# Power.net
KiCad netlist of a schematic drawn in Altium Designer
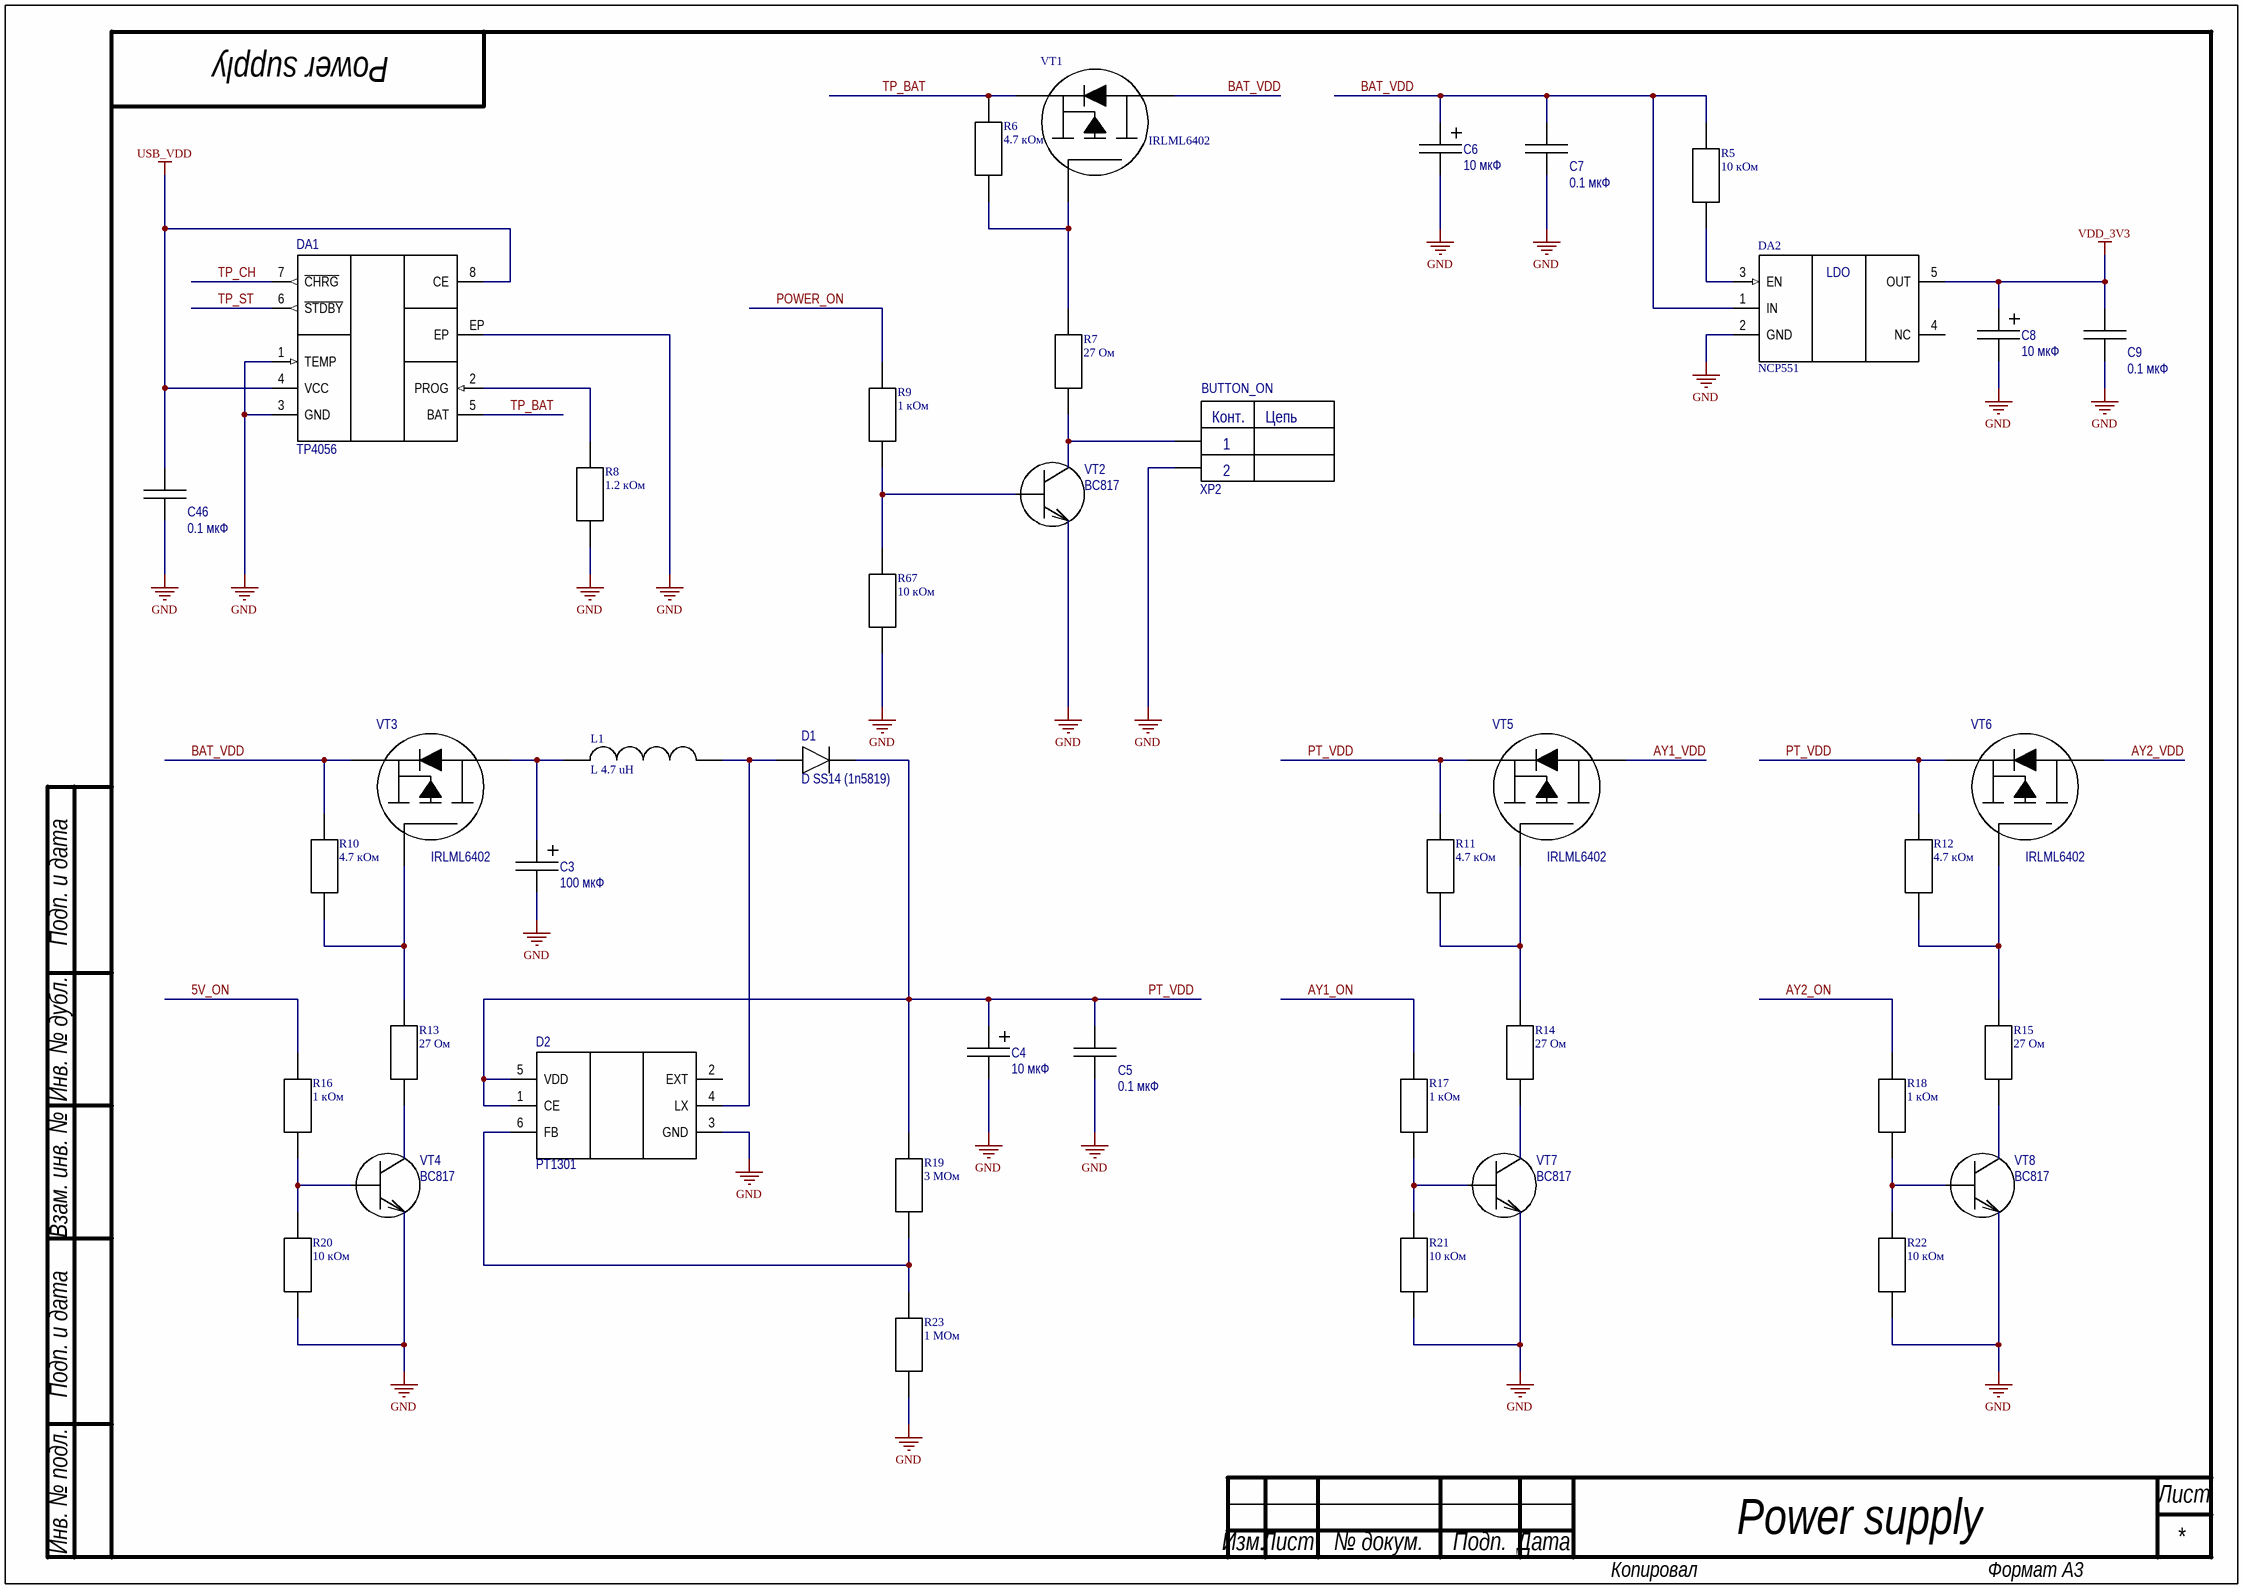
[diagram p0: Power.SchDoc]

(export (version "E")
  (design (tool "Eeschema 10.0.6"))
  (components
    (comp (ref "C3")
      (value "100 мкФ")
      (footprint "C TAN_D")
      (description "SMD Tantalium Capacitor D")
      (fields
        (field (name "TOLERANCE") "/Укажите допуск в процентах/")
        (field (name "MANUFACTURER") "/Укажите компанию-производителя/")
      )
      (libsource (lib "my_lib") (part "CAP TAN_D"))
    )
    (comp (ref "C4")
      (value "10 мкФ")
      (footprint "C TAN_C")
      (description "SMD Tantalium Capacitor C")
      (fields
        (field (name "TOLERANCE") "/Укажите допуск в процентах/")
        (field (name "MANUFACTURER") "/Укажите компанию-производителя/")
      )
      (libsource (lib "my_lib") (part "CAP TAN_C"))
    )
    (comp (ref "C5")
      (value "0.1 мкФ")
      (footprint "C 1206")
      (description "SMD Capacitor 1206")
      (fields
        (field (name "TOLERANCE") "/Укажите допуск в процентах/")
        (field (name "MANUFACTURER") "/Укажите компанию-производителя/")
      )
      (libsource (lib "my_lib") (part "CAP 1206"))
    )
    (comp (ref "C6")
      (value "10 мкФ")
      (footprint "C TAN_C")
      (description "SMD Tantalium Capacitor C")
      (fields
        (field (name "TOLERANCE") "/Укажите допуск в процентах/")
        (field (name "MANUFACTURER") "/Укажите компанию-производителя/")
      )
      (libsource (lib "my_lib") (part "CAP TAN_C"))
    )
    (comp (ref "C7")
      (value "0.1 мкФ")
      (footprint "C 1206")
      (description "SMD Capacitor 1206")
      (fields
        (field (name "TOLERANCE") "/Укажите допуск в процентах/")
        (field (name "MANUFACTURER") "/Укажите компанию-производителя/")
      )
      (libsource (lib "my_lib") (part "CAP 1206"))
    )
    (comp (ref "C8")
      (value "10 мкФ")
      (footprint "C TAN_C")
      (description "SMD Tantalium Capacitor C")
      (fields
        (field (name "TOLERANCE") "/Укажите допуск в процентах/")
        (field (name "MANUFACTURER") "/Укажите компанию-производителя/")
      )
      (libsource (lib "my_lib") (part "CAP TAN_C"))
    )
    (comp (ref "C9")
      (value "0.1 мкФ")
      (footprint "C 1206")
      (description "SMD Capacitor 1206")
      (fields
        (field (name "TOLERANCE") "/Укажите допуск в процентах/")
        (field (name "MANUFACTURER") "/Укажите компанию-производителя/")
      )
      (libsource (lib "my_lib") (part "CAP 1206"))
    )
    (comp (ref "C46")
      (value "0.1 мкФ")
      (footprint "C 1206")
      (description "SMD Capacitor 1206")
      (fields
        (field (name "TOLERANCE") "/Укажите допуск в процентах/")
        (field (name "MANUFACTURER") "/Укажите компанию-производителя/")
      )
      (libsource (lib "my_lib") (part "CAP 1206"))
    )
    (comp (ref "D1")
      (value "D SS14 (1n5819)")
      (footprint "SMA/DO-214AC")
      (libsource (lib "my_lib") (part "D SS14 (1n5819)"))
    )
    (comp (ref "D2")
      (value "PT1301")
      (footprint "SOT-23-6")
      (description "DC-DC step-up (повышающий) PT1301 в корпусе SOT23-6.")
      (libsource (lib "my_lib") (part "PT1301"))
    )
    (comp (ref "DA1") (value "TP4056") (footprint "HSOP-8") (libsource (lib "my_lib") (part "TP4056")))
    (comp (ref "DA2") (value "NCP551") (footprint "TSOP-5") (libsource (lib "my_lib") (part "NCP551")))
    (comp (ref "L1")
      (value "L 4.7 uH")
      (footprint "CD43")
      (description "Катушка индуктивности 4.7 мкГн корпус CD43 (индуктивность 4.7 uH).")
      (libsource (lib "my_lib") (part "L 4.7 uH"))
    )
    (comp (ref "R5") (value "10 кОм") (footprint "RES 0805") (libsource (lib "my_lib") (part "RES 0805")))
    (comp (ref "R6") (value "4.7 кОм") (footprint "RES 0805") (libsource (lib "my_lib") (part "RES 0805")))
    (comp (ref "R7") (value "27 Ом") (footprint "RES 0805") (libsource (lib "my_lib") (part "RES 0805")))
    (comp (ref "R8") (value "1.2 кОм") (footprint "RES 0805") (libsource (lib "my_lib") (part "RES 0805")))
    (comp (ref "R9") (value "1 кОм") (footprint "RES 0805") (libsource (lib "my_lib") (part "RES 0805")))
    (comp (ref "R10") (value "4.7 кОм") (footprint "RES 0805") (libsource (lib "my_lib") (part "RES 0805")))
    (comp (ref "R11") (value "4.7 кОм") (footprint "RES 0805") (libsource (lib "my_lib") (part "RES 0805")))
    (comp (ref "R12") (value "4.7 кОм") (footprint "RES 0805") (libsource (lib "my_lib") (part "RES 0805")))
    (comp (ref "R13") (value "27 Ом") (footprint "RES 0805") (libsource (lib "my_lib") (part "RES 0805")))
    (comp (ref "R14") (value "27 Ом") (footprint "RES 0805") (libsource (lib "my_lib") (part "RES 0805")))
    (comp (ref "R15") (value "27 Ом") (footprint "RES 0805") (libsource (lib "my_lib") (part "RES 0805")))
    (comp (ref "R16") (value "1 кОм") (footprint "RES 0805") (libsource (lib "my_lib") (part "RES 0805")))
    (comp (ref "R17") (value "1 кОм") (footprint "RES 0805") (libsource (lib "my_lib") (part "RES 0805")))
    (comp (ref "R18") (value "1 кОм") (footprint "RES 0805") (libsource (lib "my_lib") (part "RES 0805")))
    (comp (ref "R19") (value "3 МОм") (footprint "RES 0805") (libsource (lib "my_lib") (part "RES 0805")))
    (comp (ref "R20") (value "10 кОм") (footprint "RES 0805") (libsource (lib "my_lib") (part "RES 0805")))
    (comp (ref "R21") (value "10 кОм") (footprint "RES 0805") (libsource (lib "my_lib") (part "RES 0805")))
    (comp (ref "R22") (value "10 кОм") (footprint "RES 0805") (libsource (lib "my_lib") (part "RES 0805")))
    (comp (ref "R23") (value "1 МОм") (footprint "RES 0805") (libsource (lib "my_lib") (part "RES 0805")))
    (comp (ref "R67") (value "10 кОм") (footprint "RES 0805") (libsource (lib "my_lib") (part "RES 0805")))
    (comp (ref "VT1") (value "IRLML6402") (footprint "SOT-23") (libsource (lib "my_lib") (part "IRLML6402")))
    (comp (ref "VT2")
      (value "BC817")
      (footprint "SOT-23")
      (description "NPN general-purpose transistor")
      (fields (field (name "MANUFACTURER") "NXP"))
      (libsource (lib "my_lib") (part "BC817"))
    )
    (comp (ref "VT3") (value "IRLML6402") (footprint "SOT-23") (libsource (lib "my_lib") (part "IRLML6402")))
    (comp (ref "VT4")
      (value "BC817")
      (footprint "SOT-23")
      (description "NPN general-purpose transistor")
      (fields (field (name "MANUFACTURER") "NXP"))
      (libsource (lib "my_lib") (part "BC817"))
    )
    (comp (ref "VT5") (value "IRLML6402") (footprint "SOT-23") (libsource (lib "my_lib") (part "IRLML6402")))
    (comp (ref "VT6") (value "IRLML6402") (footprint "SOT-23") (libsource (lib "my_lib") (part "IRLML6402")))
    (comp (ref "VT7")
      (value "BC817")
      (footprint "SOT-23")
      (description "NPN general-purpose transistor")
      (fields (field (name "MANUFACTURER") "NXP"))
      (libsource (lib "my_lib") (part "BC817"))
    )
    (comp (ref "VT8")
      (value "BC817")
      (footprint "SOT-23")
      (description "NPN general-purpose transistor")
      (fields (field (name "MANUFACTURER") "NXP"))
      (libsource (lib "my_lib") (part "BC817"))
    )
    (comp (ref "XP2")
      (value "PLS-2")
      (footprint "PLS-2")
      (description "PLS connector")
      (fields (field (name "MANUFACTURER") "NONAME"))
      (libsource (lib "my_lib") (part "PLS-2"))
    )
  )
  (nets
    (net (code "1") (name "/5V_ON") (class "Default")
      (node (ref "R16") (pin "2") (pinfunction "2_2") (pintype "passive"))
    )
    (net (code "2") (name "/AY1_ON") (class "Default")
      (node (ref "R17") (pin "2") (pinfunction "2_2") (pintype "passive"))
    )
    (net (code "3") (name "/AY1_VDD") (class "Default")
      (node (ref "VT5") (pin "3") (pinfunction "D_3") (pintype "passive"))
    )
    (net (code "4") (name "/AY2_ON") (class "Default")
      (node (ref "R18") (pin "2") (pinfunction "2_2") (pintype "passive"))
    )
    (net (code "5") (name "/AY2_VDD") (class "Default")
      (node (ref "VT6") (pin "3") (pinfunction "D_3") (pintype "passive"))
    )
    (net (code "6") (name "/BAT_VDD") (class "Default")
      (node (ref "C6") (pin "1") (pinfunction "1_1") (pintype "passive"))
      (node (ref "C7") (pin "1") (pinfunction "1_1") (pintype "passive"))
      (node (ref "DA2") (pin "1") (pinfunction "IN_1") (pintype "passive"))
      (node (ref "R10") (pin "2") (pinfunction "2_2") (pintype "passive"))
      (node (ref "R5") (pin "2") (pinfunction "2_2") (pintype "passive"))
      (node (ref "VT1") (pin "3") (pinfunction "D_3") (pintype "passive"))
      (node (ref "VT3") (pin "2") (pinfunction "S_2") (pintype "passive"))
    )
    (net (code "7") (name "/POWER_ON") (class "Default")
      (node (ref "R9") (pin "2") (pinfunction "2_2") (pintype "passive"))
    )
    (net (code "8") (name "/PT_VDD") (class "Default")
      (node (ref "C4") (pin "1") (pinfunction "1_1") (pintype "passive"))
      (node (ref "C5") (pin "1") (pinfunction "1_1") (pintype "passive"))
      (node (ref "D1") (pin "C") (pinfunction "C_C") (pintype "passive"))
      (node (ref "D2") (pin "1") (pinfunction "CE_1") (pintype "passive"))
      (node (ref "D2") (pin "5") (pinfunction "VDD_5") (pintype "passive"))
      (node (ref "R11") (pin "2") (pinfunction "2_2") (pintype "passive"))
      (node (ref "R12") (pin "2") (pinfunction "2_2") (pintype "passive"))
      (node (ref "R19") (pin "2") (pinfunction "2_2") (pintype "passive"))
      (node (ref "VT5") (pin "2") (pinfunction "S_2") (pintype "passive"))
      (node (ref "VT6") (pin "2") (pinfunction "S_2") (pintype "passive"))
    )
    (net (code "9") (name "/TP_BAT") (class "Default")
      (node (ref "DA1") (pin "5") (pinfunction "BAT_5") (pintype "power_in"))
      (node (ref "R6") (pin "2") (pinfunction "2_2") (pintype "passive"))
      (node (ref "VT1") (pin "2") (pinfunction "S_2") (pintype "passive"))
    )
    (net (code "10") (name "/TP_CH") (class "Default")
      (node (ref "DA1") (pin "7") (pinfunction "~{CHRG}_7") (pintype "output"))
    )
    (net (code "11") (name "/TP_ST") (class "Default")
      (node (ref "DA1") (pin "6") (pinfunction "~{STDBY}_6") (pintype "output"))
    )
    (net (code "12") (name "GND") (class "Default")
      (node (ref "C3") (pin "2") (pinfunction "2_2") (pintype "passive"))
      (node (ref "C4") (pin "2") (pinfunction "2_2") (pintype "passive"))
      (node (ref "C46") (pin "2") (pinfunction "2_2") (pintype "passive"))
      (node (ref "C5") (pin "2") (pinfunction "2_2") (pintype "passive"))
      (node (ref "C6") (pin "2") (pinfunction "2_2") (pintype "passive"))
      (node (ref "C7") (pin "2") (pinfunction "2_2") (pintype "passive"))
      (node (ref "C8") (pin "2") (pinfunction "2_2") (pintype "passive"))
      (node (ref "C9") (pin "2") (pinfunction "2_2") (pintype "passive"))
      (node (ref "D2") (pin "3") (pinfunction "GND_3") (pintype "passive"))
      (node (ref "DA1") (pin "1") (pinfunction "TEMP_1") (pintype "input"))
      (node (ref "DA1") (pin "3") (pinfunction "GND_3") (pintype "power_in"))
      (node (ref "DA1") (pin "EP") (pinfunction "EP_EP") (pintype "passive"))
      (node (ref "DA2") (pin "2") (pinfunction "GND_2") (pintype "passive"))
      (node (ref "R20") (pin "1") (pinfunction "1_1") (pintype "passive"))
      (node (ref "R21") (pin "1") (pinfunction "1_1") (pintype "passive"))
      (node (ref "R22") (pin "1") (pinfunction "1_1") (pintype "passive"))
      (node (ref "R23") (pin "1") (pinfunction "1_1") (pintype "passive"))
      (node (ref "R67") (pin "1") (pinfunction "1_1") (pintype "passive"))
      (node (ref "R8") (pin "1") (pinfunction "1_1") (pintype "passive"))
      (node (ref "VT2") (pin "2") (pinfunction "E_2") (pintype "passive"))
      (node (ref "VT4") (pin "2") (pinfunction "E_2") (pintype "passive"))
      (node (ref "VT7") (pin "2") (pinfunction "E_2") (pintype "passive"))
      (node (ref "VT8") (pin "2") (pinfunction "E_2") (pintype "passive"))
      (node (ref "XP2") (pin "2") (pinfunction "2_2") (pintype "passive"))
    )
    (net (code "13") (name "Net-(D2-FB)") (class "Default")
      (node (ref "D2") (pin "6") (pinfunction "FB_6") (pintype "passive"))
      (node (ref "R19") (pin "1") (pinfunction "1_1") (pintype "passive"))
      (node (ref "R23") (pin "2") (pinfunction "2_2") (pintype "passive"))
    )
    (net (code "14") (name "Net-(D2-LX)") (class "Default")
      (node (ref "D1") (pin "A") (pinfunction "A_A") (pintype "passive"))
      (node (ref "D2") (pin "4") (pinfunction "LX_4") (pintype "passive"))
      (node (ref "L1") (pin "2") (pinfunction "2_2") (pintype "passive"))
    )
    (net (code "15") (name "Net-(DA1-PROG)") (class "Default")
      (node (ref "DA1") (pin "2") (pinfunction "PROG_2") (pintype "input"))
      (node (ref "R8") (pin "2") (pinfunction "2_2") (pintype "passive"))
    )
    (net (code "16") (name "Net-(DA2-EN)") (class "Default")
      (node (ref "DA2") (pin "3") (pinfunction "EN_3") (pintype "input"))
      (node (ref "R5") (pin "1") (pinfunction "1_1") (pintype "passive"))
    )
    (net (code "17") (name "Net-(VT1-G)") (class "Default")
      (node (ref "R6") (pin "1") (pinfunction "1_1") (pintype "passive"))
      (node (ref "R7") (pin "2") (pinfunction "2_2") (pintype "passive"))
      (node (ref "VT1") (pin "1") (pinfunction "G_1") (pintype "passive"))
    )
    (net (code "18") (name "Net-(VT2-B)") (class "Default")
      (node (ref "R67") (pin "2") (pinfunction "2_2") (pintype "passive"))
      (node (ref "R9") (pin "1") (pinfunction "1_1") (pintype "passive"))
      (node (ref "VT2") (pin "1") (pinfunction "B_1") (pintype "passive"))
    )
    (net (code "19") (name "Net-(VT2-C)") (class "Default")
      (node (ref "R7") (pin "1") (pinfunction "1_1") (pintype "passive"))
      (node (ref "VT2") (pin "3") (pinfunction "C_3") (pintype "passive"))
      (node (ref "XP2") (pin "1") (pinfunction "1_1") (pintype "passive"))
    )
    (net (code "20") (name "Net-(VT3-D)") (class "Default")
      (node (ref "C3") (pin "1") (pinfunction "1_1") (pintype "passive"))
      (node (ref "L1") (pin "1") (pinfunction "1_1") (pintype "passive"))
      (node (ref "VT3") (pin "3") (pinfunction "D_3") (pintype "passive"))
    )
    (net (code "21") (name "Net-(VT3-G)") (class "Default")
      (node (ref "R10") (pin "1") (pinfunction "1_1") (pintype "passive"))
      (node (ref "R13") (pin "2") (pinfunction "2_2") (pintype "passive"))
      (node (ref "VT3") (pin "1") (pinfunction "G_1") (pintype "passive"))
    )
    (net (code "22") (name "Net-(VT4-B)") (class "Default")
      (node (ref "R16") (pin "1") (pinfunction "1_1") (pintype "passive"))
      (node (ref "R20") (pin "2") (pinfunction "2_2") (pintype "passive"))
      (node (ref "VT4") (pin "1") (pinfunction "B_1") (pintype "passive"))
    )
    (net (code "23") (name "Net-(VT4-C)") (class "Default")
      (node (ref "R13") (pin "1") (pinfunction "1_1") (pintype "passive"))
      (node (ref "VT4") (pin "3") (pinfunction "C_3") (pintype "passive"))
    )
    (net (code "24") (name "Net-(VT5-G)") (class "Default")
      (node (ref "R11") (pin "1") (pinfunction "1_1") (pintype "passive"))
      (node (ref "R14") (pin "2") (pinfunction "2_2") (pintype "passive"))
      (node (ref "VT5") (pin "1") (pinfunction "G_1") (pintype "passive"))
    )
    (net (code "25") (name "Net-(VT6-G)") (class "Default")
      (node (ref "R12") (pin "1") (pinfunction "1_1") (pintype "passive"))
      (node (ref "R15") (pin "2") (pinfunction "2_2") (pintype "passive"))
      (node (ref "VT6") (pin "1") (pinfunction "G_1") (pintype "passive"))
    )
    (net (code "26") (name "Net-(VT7-B)") (class "Default")
      (node (ref "R17") (pin "1") (pinfunction "1_1") (pintype "passive"))
      (node (ref "R21") (pin "2") (pinfunction "2_2") (pintype "passive"))
      (node (ref "VT7") (pin "1") (pinfunction "B_1") (pintype "passive"))
    )
    (net (code "27") (name "Net-(VT7-C)") (class "Default")
      (node (ref "R14") (pin "1") (pinfunction "1_1") (pintype "passive"))
      (node (ref "VT7") (pin "3") (pinfunction "C_3") (pintype "passive"))
    )
    (net (code "28") (name "Net-(VT8-B)") (class "Default")
      (node (ref "R18") (pin "1") (pinfunction "1_1") (pintype "passive"))
      (node (ref "R22") (pin "2") (pinfunction "2_2") (pintype "passive"))
      (node (ref "VT8") (pin "1") (pinfunction "B_1") (pintype "passive"))
    )
    (net (code "29") (name "Net-(VT8-C)") (class "Default")
      (node (ref "R15") (pin "1") (pinfunction "1_1") (pintype "passive"))
      (node (ref "VT8") (pin "3") (pinfunction "C_3") (pintype "passive"))
    )
    (net (code "30") (name "USB_VDD") (class "Default")
      (node (ref "C46") (pin "1") (pinfunction "1_1") (pintype "passive"))
      (node (ref "DA1") (pin "4") (pinfunction "VCC_4") (pintype "power_in"))
      (node (ref "DA1") (pin "8") (pinfunction "CE_8") (pintype "passive"))
    )
    (net (code "31") (name "VDD_3V3") (class "Default")
      (node (ref "C8") (pin "1") (pinfunction "1_1") (pintype "passive"))
      (node (ref "C9") (pin "1") (pinfunction "1_1") (pintype "passive"))
      (node (ref "DA2") (pin "5") (pinfunction "OUT_5") (pintype "passive"))
    )
    (net (code "32") (name "unconnected-(D2-EXT-Pad2)") (class "Default")
      (node (ref "D2") (pin "2") (pinfunction "EXT_2") (pintype "passive"))
    )
    (net (code "33") (name "unconnected-(DA2-NC-Pad4)") (class "Default")
      (node (ref "DA2") (pin "4") (pinfunction "NC_4") (pintype "passive"))
    )
  )
)
